# samSchem.net
KiCad netlist of a schematic drawn in EAGLE
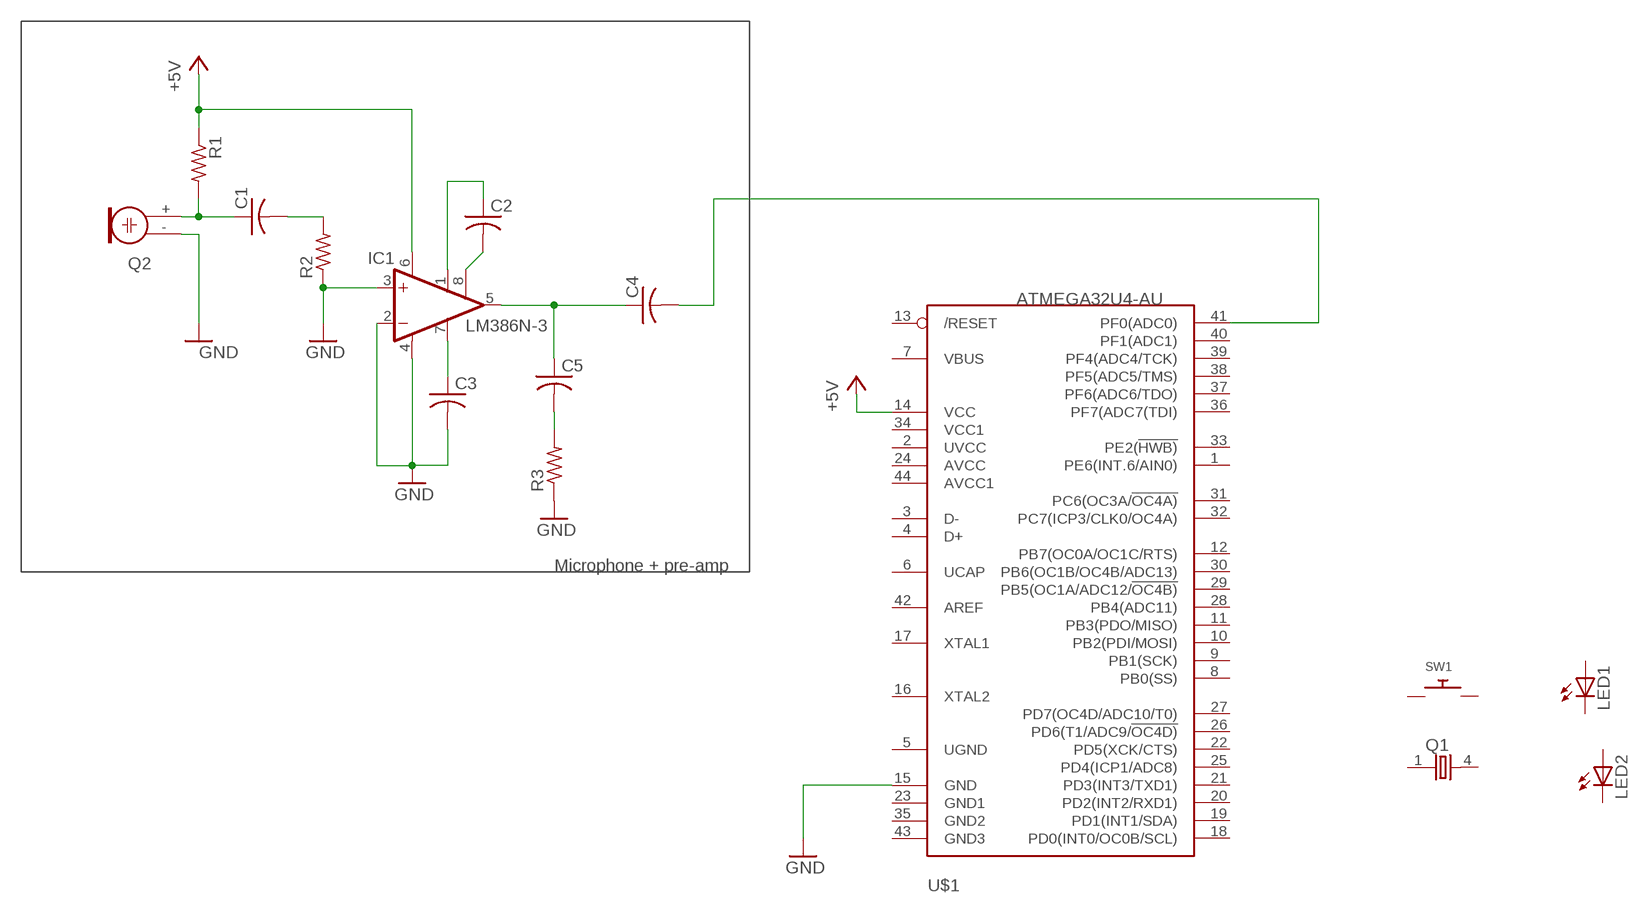
[diagram p0: schematic, sheet 1]

(export (version "E")
  (design (tool "Eeschema 10.0.6"))
  (components
    (comp (ref "C1")
      (value "C-USC0805")
      (footprint "eagle-import:C0805")
      (libsource (lib "eagle-import") (part "C-USC0805"))
    )
    (comp (ref "C2")
      (value "C-USC0805")
      (footprint "eagle-import:C0805")
      (libsource (lib "eagle-import") (part "C-USC0805"))
    )
    (comp (ref "C3")
      (value "C-USC0805")
      (footprint "eagle-import:C0805")
      (libsource (lib "eagle-import") (part "C-USC0805"))
    )
    (comp (ref "C4")
      (value "C-USC0805")
      (footprint "eagle-import:C0805")
      (libsource (lib "eagle-import") (part "C-USC0805"))
    )
    (comp (ref "C5")
      (value "C-USC0805")
      (footprint "eagle-import:C0805")
      (libsource (lib "eagle-import") (part "C-USC0805"))
    )
    (comp (ref "IC1")
      (value "LM386N-3")
      (footprint "eagle-import:DIL08")
      (libsource (lib "eagle-import") (part "LM386?-N3"))
    )
    (comp (ref "LED1")
      (value "LEDCHIP-LED0805")
      (footprint "eagle-import:CHIP-LED0805")
      (libsource (lib "eagle-import") (part "LEDCHIP-LED0805"))
    )
    (comp (ref "LED2")
      (value "LEDCHIP-LED0805")
      (footprint "eagle-import:CHIP-LED0805")
      (libsource (lib "eagle-import") (part "LEDCHIP-LED0805"))
    )
    (comp (ref "Q1")
      (value "86SMX")
      (footprint "eagle-import:86SMX")
      (fields (field (name "MF") "C-MAC  FREQUENCY PRODUCTS LTD") (field (name "MPN") "XTAL003321- 86SMX"))
      (libsource (lib "eagle-import") (part "86SMX"))
    )
    (comp (ref "Q2")
      (value "ELECTRET")
      (footprint "eagle-import:9.7ELECTRET")
      (libsource (lib "eagle-import") (part "ELECTRET"))
    )
    (comp (ref "R1")
      (value "R-US_M0805")
      (footprint "eagle-import:M0805")
      (libsource (lib "eagle-import") (part "R-US_M0805"))
    )
    (comp (ref "R2")
      (value "R-US_M0805")
      (footprint "eagle-import:M0805")
      (libsource (lib "eagle-import") (part "R-US_M0805"))
    )
    (comp (ref "R3")
      (value "R-US_M0805")
      (footprint "eagle-import:M0805")
      (libsource (lib "eagle-import") (part "R-US_M0805"))
    )
    (comp (ref "SW1")
      (value "SWITCH_PUSHBUTTONSOFTTOUCHSMD_SJ")
      (footprint "eagle-import:PUSHBUTTON_SMD_SJ")
      (libsource (lib "eagle-import") (part "SWITCH_PUSHBUTTONSOFTTOUCHSMD_SJ"))
    )
    (comp (ref "U$1")
      (value "ATMEGA32U4-AU")
      (footprint "eagle-import:TQFP44")
      (libsource (lib "eagle-import") (part "ATMEGA32U4-AU"))
    )
  )
  (nets
    (net (code "1") (name "+5V") (class "Default")
      (node (ref "IC1") (pin "6") (pinfunction "VS_6") (pintype "power_in"))
      (node (ref "R1") (pin "1") (pinfunction "1_1") (pintype "passive"))
      (node (ref "U$1") (pin "14") (pinfunction "VCC_14") (pintype "bidirectional"))
    )
    (net (code "2") (name "GND") (class "Default")
      (node (ref "C3") (pin "2") (pinfunction "2_2") (pintype "passive"))
      (node (ref "IC1") (pin "2") (pinfunction "-IN_2") (pintype "input"))
      (node (ref "IC1") (pin "3") (pinfunction "+IN_3") (pintype "input"))
      (node (ref "IC1") (pin "4") (pinfunction "GND_4") (pintype "power_in"))
      (node (ref "Q2") (pin "-") (pinfunction "1_-") (pintype "passive"))
      (node (ref "R2") (pin "1") (pinfunction "1_1") (pintype "passive"))
      (node (ref "R3") (pin "1") (pinfunction "1_1") (pintype "passive"))
      (node (ref "U$1") (pin "15") (pinfunction "GND_15") (pintype "bidirectional"))
    )
    (net (code "3") (name "Net-(C1-Pad2)") (class "Default")
      (node (ref "C1") (pin "2") (pinfunction "2_2") (pintype "passive"))
      (node (ref "R2") (pin "2") (pinfunction "2_2") (pintype "passive"))
    )
    (net (code "4") (name "Net-(C2-Pad1)") (class "Default")
      (node (ref "C2") (pin "1") (pinfunction "1_1") (pintype "passive"))
      (node (ref "IC1") (pin "1") (pinfunction "GAIN_1") (pintype "passive"))
    )
    (net (code "5") (name "Net-(C2-Pad2)") (class "Default")
      (node (ref "C2") (pin "2") (pinfunction "2_2") (pintype "passive"))
      (node (ref "IC1") (pin "8") (pinfunction "GAIN_8") (pintype "passive"))
    )
    (net (code "6") (name "Net-(C5-Pad2)") (class "Default")
      (node (ref "C5") (pin "2") (pinfunction "2_2") (pintype "passive"))
      (node (ref "R3") (pin "2") (pinfunction "2_2") (pintype "passive"))
    )
    (net (code "7") (name "Net-(IC1-BYPASS)") (class "Default")
      (node (ref "C3") (pin "1") (pinfunction "1_1") (pintype "passive"))
      (node (ref "IC1") (pin "7") (pinfunction "BYPASS_7") (pintype "passive"))
    )
    (net (code "8") (name "Net-(IC1-OUT)") (class "Default")
      (node (ref "C4") (pin "1") (pinfunction "1_1") (pintype "passive"))
      (node (ref "C5") (pin "1") (pinfunction "1_1") (pintype "passive"))
      (node (ref "IC1") (pin "5") (pinfunction "OUT_5") (pintype "output"))
    )
    (net (code "9") (name "Net-(Q2-2)") (class "Default")
      (node (ref "C1") (pin "1") (pinfunction "1_1") (pintype "passive"))
      (node (ref "Q2") (pin "+") (pinfunction "2_+") (pintype "passive"))
      (node (ref "R1") (pin "2") (pinfunction "2_2") (pintype "passive"))
    )
    (net (code "10") (name "Net-(U$1-PF0(ADC0))") (class "Default")
      (node (ref "C4") (pin "2") (pinfunction "2_2") (pintype "passive"))
      (node (ref "U$1") (pin "41") (pinfunction "PF0(ADC0)_41") (pintype "bidirectional"))
    )
    (net (code "11") (name "unconnected-(LED1-PadA)") (class "Default")
      (node (ref "LED1") (pin "A") (pinfunction "A_A") (pintype "passive"))
    )
    (net (code "12") (name "unconnected-(LED1-PadC)") (class "Default")
      (node (ref "LED1") (pin "C") (pinfunction "C_C") (pintype "passive"))
    )
    (net (code "13") (name "unconnected-(LED2-PadA)") (class "Default")
      (node (ref "LED2") (pin "A") (pinfunction "A_A") (pintype "passive"))
    )
    (net (code "14") (name "unconnected-(LED2-PadC)") (class "Default")
      (node (ref "LED2") (pin "C") (pinfunction "C_C") (pintype "passive"))
    )
    (net (code "15") (name "unconnected-(Q1-2-Pad4)") (class "Default")
      (node (ref "Q1") (pin "4") (pinfunction "2_4") (pintype "passive"))
    )
    (net (code "16") (name "unconnected-(Q1-Pad1)") (class "Default")
      (node (ref "Q1") (pin "1") (pinfunction "1_1") (pintype "passive"))
    )
    (net (code "17") (name "unconnected-(SW1-PadP$1)") (class "Default")
      (node (ref "SW1") (pin "P$1") (pinfunction "P$1_P$1") (pintype "passive"))
    )
    (net (code "18") (name "unconnected-(SW1-PadP$2)") (class "Default")
      (node (ref "SW1") (pin "P$2") (pinfunction "P$2_P$2") (pintype "passive"))
    )
    (net (code "19") (name "unconnected-(U$1-AREF-Pad42)") (class "Default")
      (node (ref "U$1") (pin "42") (pinfunction "AREF_42") (pintype "bidirectional"))
    )
    (net (code "20") (name "unconnected-(U$1-AVCC-Pad24)") (class "Default")
      (node (ref "U$1") (pin "24") (pinfunction "AVCC_24") (pintype "bidirectional"))
    )
    (net (code "21") (name "unconnected-(U$1-AVCC1-Pad44)") (class "Default")
      (node (ref "U$1") (pin "44") (pinfunction "AVCC1_44") (pintype "bidirectional"))
    )
    (net (code "22") (name "unconnected-(U$1-D+-Pad4)") (class "Default")
      (node (ref "U$1") (pin "4") (pinfunction "D+_4") (pintype "bidirectional"))
    )
    (net (code "23") (name "unconnected-(U$1-D--Pad3)") (class "Default")
      (node (ref "U$1") (pin "3") (pinfunction "D-_3") (pintype "bidirectional"))
    )
    (net (code "24") (name "unconnected-(U$1-GND1-Pad23)") (class "Default")
      (node (ref "U$1") (pin "23") (pinfunction "GND1_23") (pintype "bidirectional"))
    )
    (net (code "25") (name "unconnected-(U$1-GND2-Pad35)") (class "Default")
      (node (ref "U$1") (pin "35") (pinfunction "GND2_35") (pintype "bidirectional"))
    )
    (net (code "26") (name "unconnected-(U$1-GND3-Pad43)") (class "Default")
      (node (ref "U$1") (pin "43") (pinfunction "GND3_43") (pintype "bidirectional"))
    )
    (net (code "27") (name "unconnected-(U$1-PB0(SS)-Pad8)") (class "Default")
      (node (ref "U$1") (pin "8") (pinfunction "PB0(SS)_8") (pintype "bidirectional"))
    )
    (net (code "28") (name "unconnected-(U$1-PB1(SCK)-Pad9)") (class "Default")
      (node (ref "U$1") (pin "9") (pinfunction "PB1(SCK)_9") (pintype "bidirectional"))
    )
    (net (code "29") (name "unconnected-(U$1-PB2(PDI{slash}MOSI)-Pad10)") (class "Default")
      (node (ref "U$1") (pin "10") (pinfunction "PB2(PDI/MOSI)_10") (pintype "bidirectional"))
    )
    (net (code "30") (name "unconnected-(U$1-PB3(PDO{slash}MISO)-Pad11)") (class "Default")
      (node (ref "U$1") (pin "11") (pinfunction "PB3(PDO/MISO)_11") (pintype "bidirectional"))
    )
    (net (code "31") (name "unconnected-(U$1-PB4(ADC11)-Pad28)") (class "Default")
      (node (ref "U$1") (pin "28") (pinfunction "PB4(ADC11)_28") (pintype "bidirectional"))
    )
    (net (code "32") (name "unconnected-(U$1-PB5(OC1A{slash}ADC12{slash}~{OC4B})-Pad29)") (class "Default")
      (node (ref "U$1") (pin "29") (pinfunction "PB5(OC1A/ADC12/~{OC4B})_29") (pintype "bidirectional"))
    )
    (net (code "33") (name "unconnected-(U$1-PB6(OC1B{slash}OC4B{slash}ADC13)-Pad30)") (class "Default")
      (node (ref "U$1") (pin "30") (pinfunction "PB6(OC1B/OC4B/ADC13)_30") (pintype "bidirectional"))
    )
    (net (code "34") (name "unconnected-(U$1-PB7(OC0A{slash}OC1C{slash}RTS)-Pad12)") (class "Default")
      (node (ref "U$1") (pin "12") (pinfunction "PB7(OC0A/OC1C/RTS)_12") (pintype "bidirectional"))
    )
    (net (code "35") (name "unconnected-(U$1-PC6(OC3A{slash}~{OC4A})-Pad31)") (class "Default")
      (node (ref "U$1") (pin "31") (pinfunction "PC6(OC3A/~{OC4A})_31") (pintype "bidirectional"))
    )
    (net (code "36") (name "unconnected-(U$1-PC7(ICP3{slash}CLK0{slash}OC4A)-Pad32)") (class "Default")
      (node (ref "U$1") (pin "32") (pinfunction "PC7(ICP3/CLK0/OC4A)_32") (pintype "bidirectional"))
    )
    (net (code "37") (name "unconnected-(U$1-PD0(INT0{slash}OC0B{slash}SCL)-Pad18)") (class "Default")
      (node (ref "U$1") (pin "18") (pinfunction "PD0(INT0/OC0B/SCL)_18") (pintype "bidirectional"))
    )
    (net (code "38") (name "unconnected-(U$1-PD1(INT1{slash}SDA)-Pad19)") (class "Default")
      (node (ref "U$1") (pin "19") (pinfunction "PD1(INT1/SDA)_19") (pintype "bidirectional"))
    )
    (net (code "39") (name "unconnected-(U$1-PD2(INT2{slash}RXD1)-Pad20)") (class "Default")
      (node (ref "U$1") (pin "20") (pinfunction "PD2(INT2/RXD1)_20") (pintype "bidirectional"))
    )
    (net (code "40") (name "unconnected-(U$1-PD3(INT3{slash}TXD1)-Pad21)") (class "Default")
      (node (ref "U$1") (pin "21") (pinfunction "PD3(INT3/TXD1)_21") (pintype "bidirectional"))
    )
    (net (code "41") (name "unconnected-(U$1-PD4(ICP1{slash}ADC8)-Pad25)") (class "Default")
      (node (ref "U$1") (pin "25") (pinfunction "PD4(ICP1/ADC8)_25") (pintype "bidirectional"))
    )
    (net (code "42") (name "unconnected-(U$1-PD5(XCK{slash}CTS)-Pad22)") (class "Default")
      (node (ref "U$1") (pin "22") (pinfunction "PD5(XCK/CTS)_22") (pintype "bidirectional"))
    )
    (net (code "43") (name "unconnected-(U$1-PD6(T1{slash}ADC9{slash}~{OC4D})-Pad26)") (class "Default")
      (node (ref "U$1") (pin "26") (pinfunction "PD6(T1/ADC9/~{OC4D})_26") (pintype "bidirectional"))
    )
    (net (code "44") (name "unconnected-(U$1-PD7(OC4D{slash}ADC10{slash}T0)-Pad27)") (class "Default")
      (node (ref "U$1") (pin "27") (pinfunction "PD7(OC4D/ADC10/T0)_27") (pintype "bidirectional"))
    )
    (net (code "45") (name "unconnected-(U$1-PE2(~{HWB})-Pad33)") (class "Default")
      (node (ref "U$1") (pin "33") (pinfunction "PE2(~{HWB})_33") (pintype "bidirectional"))
    )
    (net (code "46") (name "unconnected-(U$1-PE6(INT.6{slash}AIN0)-Pad1)") (class "Default")
      (node (ref "U$1") (pin "1") (pinfunction "PE6(INT.6/AIN0)_1") (pintype "bidirectional"))
    )
    (net (code "47") (name "unconnected-(U$1-PF1(ADC1)-Pad40)") (class "Default")
      (node (ref "U$1") (pin "40") (pinfunction "PF1(ADC1)_40") (pintype "bidirectional"))
    )
    (net (code "48") (name "unconnected-(U$1-PF4(ADC4{slash}TCK)-Pad39)") (class "Default")
      (node (ref "U$1") (pin "39") (pinfunction "PF4(ADC4/TCK)_39") (pintype "bidirectional"))
    )
    (net (code "49") (name "unconnected-(U$1-PF5(ADC5{slash}TMS)-Pad38)") (class "Default")
      (node (ref "U$1") (pin "38") (pinfunction "PF5(ADC5/TMS)_38") (pintype "bidirectional"))
    )
    (net (code "50") (name "unconnected-(U$1-PF6(ADC6{slash}TDO)-Pad37)") (class "Default")
      (node (ref "U$1") (pin "37") (pinfunction "PF6(ADC6/TDO)_37") (pintype "bidirectional"))
    )
    (net (code "51") (name "unconnected-(U$1-PF7(ADC7(TDI)-Pad36)") (class "Default")
      (node (ref "U$1") (pin "36") (pinfunction "PF7(ADC7(TDI)_36") (pintype "bidirectional"))
    )
    (net (code "52") (name "unconnected-(U$1-UCAP-Pad6)") (class "Default")
      (node (ref "U$1") (pin "6") (pinfunction "UCAP_6") (pintype "bidirectional"))
    )
    (net (code "53") (name "unconnected-(U$1-UGND-Pad5)") (class "Default")
      (node (ref "U$1") (pin "5") (pinfunction "UGND_5") (pintype "bidirectional"))
    )
    (net (code "54") (name "unconnected-(U$1-UVCC-Pad2)") (class "Default")
      (node (ref "U$1") (pin "2") (pinfunction "UVCC_2") (pintype "bidirectional"))
    )
    (net (code "55") (name "unconnected-(U$1-VBUS-Pad7)") (class "Default")
      (node (ref "U$1") (pin "7") (pinfunction "VBUS_7") (pintype "bidirectional"))
    )
    (net (code "56") (name "unconnected-(U$1-VCC1-Pad34)") (class "Default")
      (node (ref "U$1") (pin "34") (pinfunction "VCC1_34") (pintype "bidirectional"))
    )
    (net (code "57") (name "unconnected-(U$1-XTAL1-Pad17)") (class "Default")
      (node (ref "U$1") (pin "17") (pinfunction "XTAL1_17") (pintype "bidirectional"))
    )
    (net (code "58") (name "unconnected-(U$1-XTAL2-Pad16)") (class "Default")
      (node (ref "U$1") (pin "16") (pinfunction "XTAL2_16") (pintype "bidirectional"))
    )
    (net (code "59") (name "unconnected-(U$1-{slash}RESET-Pad13)") (class "Default")
      (node (ref "U$1") (pin "13") (pinfunction "/RESET_13") (pintype "bidirectional"))
    )
  )
)
